# Adapter-Stamps-001.net
KiCad netlist of a schematic drawn in EAGLE
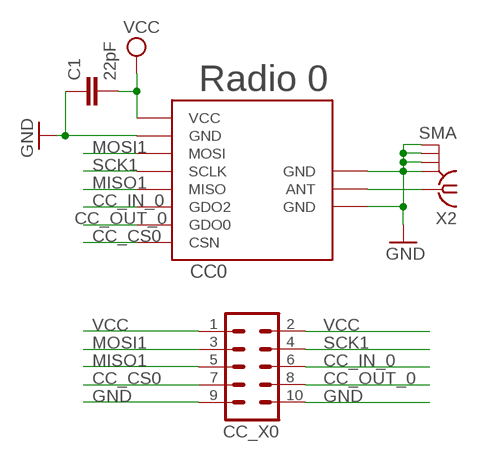
[diagram p0: schematic, sheet 1]

(export (version "E")
  (design (tool "Eeschema 10.0.6"))
  (components
    (comp (ref "C1")
      (value "22pF")
      (footprint "eagle-import:C0805")
      (libsource (lib "eagle-import") (part "C-EUC0805"))
    )
    (comp (ref "CC0")
      (value "CC1101_MODULE1SMD")
      (footprint "eagle-import:CC1101_MODULE1_SMD")
      (libsource (lib "eagle-import") (part "CC1101_MODULE1SMD"))
    )
    (comp (ref "CC_X0")
      (value "MA05-2")
      (footprint "eagle-import:MA05-2")
      (libsource (lib "eagle-import") (part "MA05-2"))
    )
    (comp (ref "X2")
      (value "SMA")
      (footprint "eagle-import:SMA")
      (libsource (lib "eagle-import") (part "SMA"))
    )
  )
  (nets
    (net (code "1") (name "/CC_CS0") (class "Default")
      (node (ref "CC0") (pin "CSN") (pinfunction "CSN_CSN") (pintype "bidirectional"))
      (node (ref "CC_X0") (pin "7") (pinfunction "7_7") (pintype "passive"))
    )
    (net (code "2") (name "/CC_IN_0") (class "Default")
      (node (ref "CC0") (pin "GDO2") (pinfunction "GDO2_GDO2") (pintype "bidirectional"))
      (node (ref "CC_X0") (pin "6") (pinfunction "6_6") (pintype "passive"))
    )
    (net (code "3") (name "/CC_OUT_0") (class "Default")
      (node (ref "CC0") (pin "GDO0") (pinfunction "GDO0_GDO0") (pintype "bidirectional"))
      (node (ref "CC_X0") (pin "8") (pinfunction "8_8") (pintype "passive"))
    )
    (net (code "4") (name "/MISO1") (class "Default")
      (node (ref "CC0") (pin "MISO") (pinfunction "MISO_MISO") (pintype "bidirectional"))
      (node (ref "CC_X0") (pin "5") (pinfunction "5_5") (pintype "passive"))
    )
    (net (code "5") (name "/MOSI1") (class "Default")
      (node (ref "CC0") (pin "MOSI") (pinfunction "MOSI_MOSI") (pintype "bidirectional"))
      (node (ref "CC_X0") (pin "3") (pinfunction "3_3") (pintype "passive"))
    )
    (net (code "6") (name "/SCK1") (class "Default")
      (node (ref "CC0") (pin "SCLK") (pinfunction "SCLK_SCLK") (pintype "bidirectional"))
      (node (ref "CC_X0") (pin "4") (pinfunction "4_4") (pintype "passive"))
    )
    (net (code "7") (name "GND") (class "Default")
      (node (ref "C1") (pin "1") (pinfunction "1_1") (pintype "passive"))
      (node (ref "CC0") (pin "GND@0") (pinfunction "GND_GND@0") (pintype "power_in"))
      (node (ref "CC0") (pin "GND@1") (pinfunction "GND_GND@1") (pintype "power_in"))
      (node (ref "CC0") (pin "GND@2") (pinfunction "GND_GND@2") (pintype "power_in"))
      (node (ref "CC_X0") (pin "10") (pinfunction "10_10") (pintype "passive"))
      (node (ref "CC_X0") (pin "9") (pinfunction "9_9") (pintype "passive"))
      (node (ref "X2") (pin "GND@1") (pinfunction "2_GND@1") (pintype "passive"))
      (node (ref "X2") (pin "GND@2") (pinfunction "3_GND@2") (pintype "passive"))
      (node (ref "X2") (pin "GND@3") (pinfunction "4_GND@3") (pintype "passive"))
      (node (ref "X2") (pin "GND@4") (pinfunction "5_GND@4") (pintype "passive"))
    )
    (net (code "8") (name "Net-(CC0-PadANT)") (class "Default")
      (node (ref "CC0") (pin "ANT") (pinfunction "ANT_ANT") (pintype "output"))
      (node (ref "X2") (pin "1") (pinfunction "1_1") (pintype "passive"))
    )
    (net (code "9") (name "VCC") (class "Default")
      (node (ref "C1") (pin "2") (pinfunction "2_2") (pintype "passive"))
      (node (ref "CC0") (pin "VCC") (pinfunction "VCC_VCC") (pintype "power_in"))
      (node (ref "CC_X0") (pin "1") (pinfunction "1_1") (pintype "passive"))
      (node (ref "CC_X0") (pin "2") (pinfunction "2_2") (pintype "passive"))
    )
  )
)
